# DS18B20.net
KiCad netlist of a schematic drawn in Altium Designer
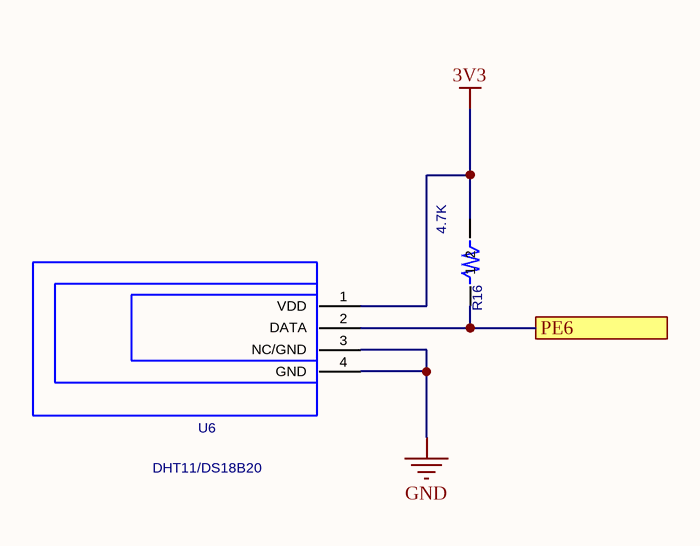
[diagram p0: DS18B20.SchDoc]

(export (version "E")
  (design (tool "Eeschema 10.0.6"))
  (components
    (comp (ref "R16")
      (value "4.7K")
      (footprint "RES_0603_FIRE")
      (description "0402")
      (fields (field (name "TOLERANCE") "+-5%") (field (name "Comment") "RES_4K7_0603_FIRE"))
      (libsource (lib "MINI-V3") (part "RES_4K7_0603_FIRE"))
    )
    (comp (ref "U6")
      (value "DHT11/DS18B20")
      (footprint "HDR1X4")
      (libsource (lib "MINI-V3") (part "DHT11/DS18B20"))
    )
  )
  (nets
    (net (code "1") (name "/PE6") (class "Default")
      (node (ref "R16") (pin "1") (pinfunction "1_1") (pintype "passive"))
      (node (ref "U6") (pin "2") (pinfunction "DATA_2") (pintype "passive"))
    )
    (net (code "2") (name "3V3") (class "Default")
      (node (ref "R16") (pin "2") (pinfunction "2_2") (pintype "passive"))
      (node (ref "U6") (pin "1") (pinfunction "VDD_1") (pintype "passive"))
    )
    (net (code "3") (name "GND") (class "Default")
      (node (ref "U6") (pin "3") (pinfunction "NC/GND_3") (pintype "passive"))
      (node (ref "U6") (pin "4") (pinfunction "GND_4") (pintype "passive"))
    )
  )
)
